# ELoad_Control_Assembly_Gen_2_-_Rev_2.net
KiCad netlist of a schematic drawn in Altium Designer
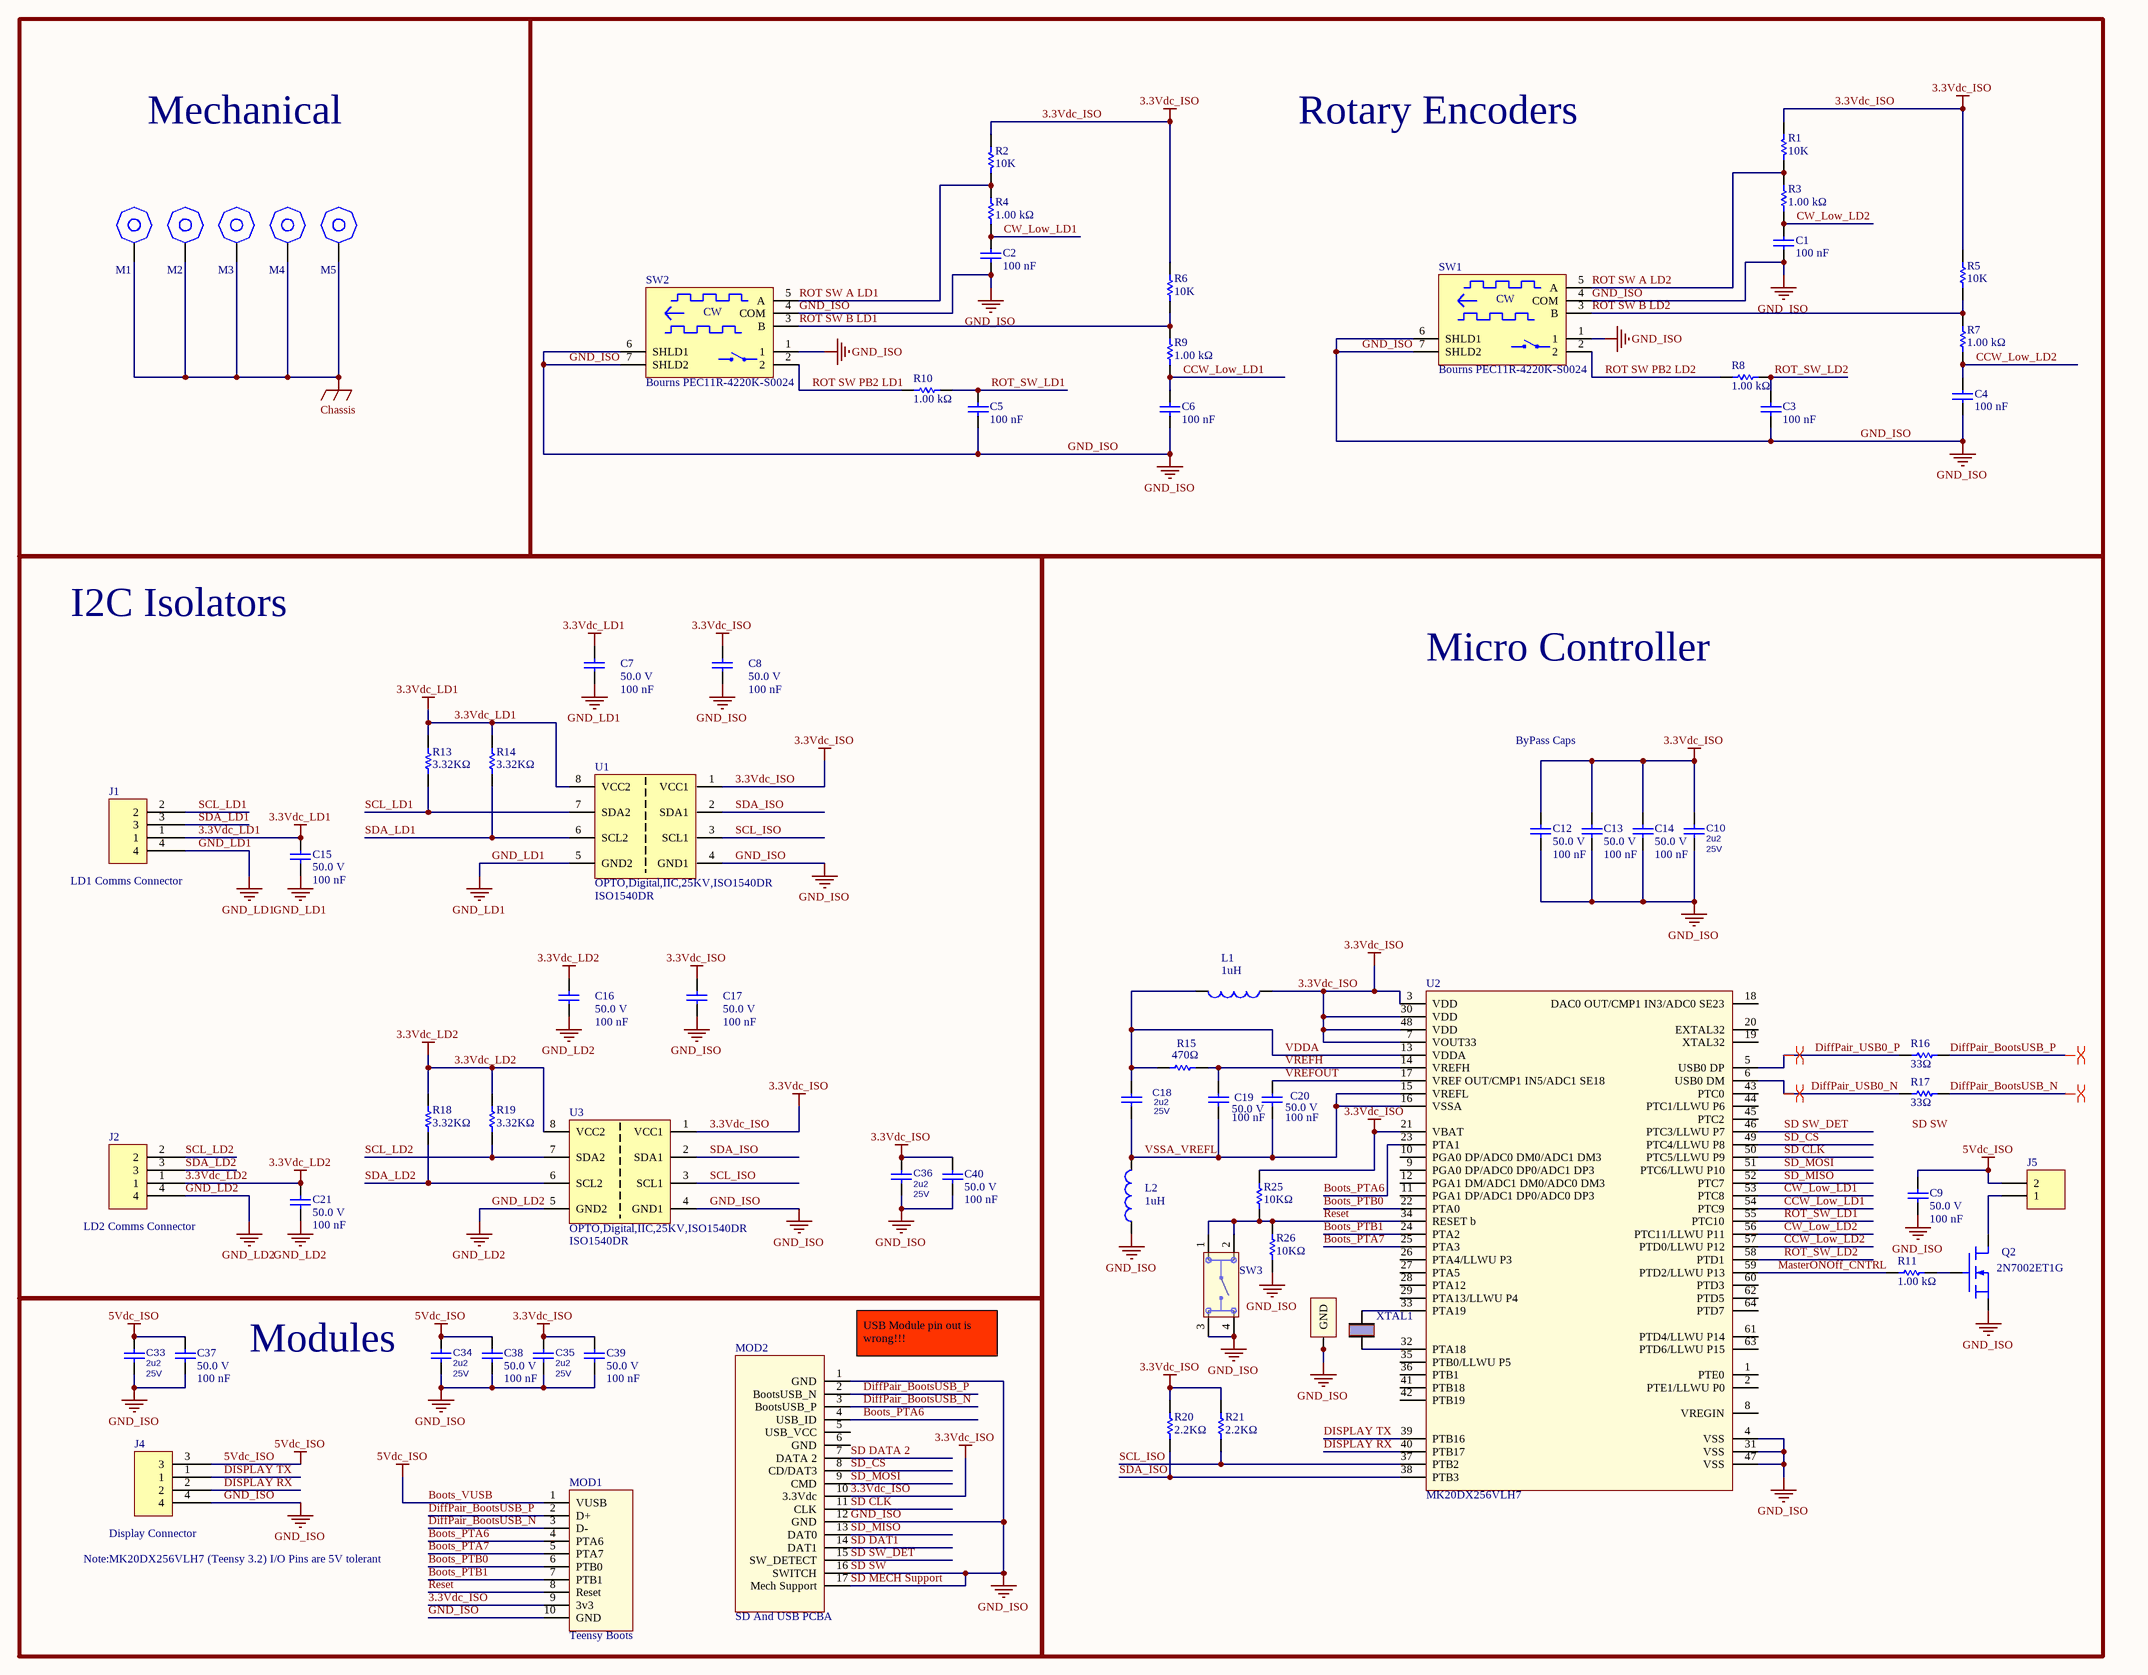
[diagram p0: ELoad Control Assembly Gen 2 - Rev 2.SchDoc]

(export (version "E")
  (design (tool "Eeschema 10.0.6"))
  (components
    (comp (ref "C1")
      (value "08055C104JAT2A")
      (footprint "CAP, 0805, HD")
      (description "Capacitor; Ceramic; Cap 0.1 uF; Tol 5%; Vol-Rtg 50 VDC; SMT; 0805; X7R; Tape & Reel")
      (fields (field (name "CAPACITANCE") "100 nF"))
      (libsource (lib "Master Oct28_2018") (part "Cap,0805,100nf,50V,5%,08055C104JAT2A"))
    )
    (comp (ref "C2")
      (value "08055C104JAT2A")
      (footprint "CAP, 0805, HD")
      (description "Capacitor; Ceramic; Cap 0.1 uF; Tol 5%; Vol-Rtg 50 VDC; SMT; 0805; X7R; Tape & Reel")
      (fields (field (name "CAPACITANCE") "100 nF"))
      (libsource (lib "Master Oct28_2018") (part "Cap,0805,100nf,50V,5%,08055C104JAT2A"))
    )
    (comp (ref "C3")
      (value "08055C104JAT2A")
      (footprint "CAP, 0805, HD")
      (description "Capacitor; Ceramic; Cap 0.1 uF; Tol 5%; Vol-Rtg 50 VDC; SMT; 0805; X7R; Tape & Reel")
      (fields (field (name "CAPACITANCE") "100 nF"))
      (libsource (lib "Master Oct28_2018") (part "Cap,0805,100nf,50V,5%,08055C104JAT2A"))
    )
    (comp (ref "C4")
      (value "08055C104JAT2A")
      (footprint "CAP, 0805, HD")
      (description "Capacitor; Ceramic; Cap 0.1 uF; Tol 5%; Vol-Rtg 50 VDC; SMT; 0805; X7R; Tape & Reel")
      (fields (field (name "CAPACITANCE") "100 nF"))
      (libsource (lib "Master Oct28_2018") (part "Cap,0805,100nf,50V,5%,08055C104JAT2A"))
    )
    (comp (ref "C5")
      (value "08055C104JAT2A")
      (footprint "CAP, 0805, HD")
      (description "Capacitor; Ceramic; Cap 0.1 uF; Tol 5%; Vol-Rtg 50 VDC; SMT; 0805; X7R; Tape & Reel")
      (fields (field (name "CAPACITANCE") "100 nF"))
      (libsource (lib "Master Oct28_2018") (part "Cap,0805,100nf,50V,5%,08055C104JAT2A"))
    )
    (comp (ref "C6")
      (value "08055C104JAT2A")
      (footprint "CAP, 0805, HD")
      (description "Capacitor; Ceramic; Cap 0.1 uF; Tol 5%; Vol-Rtg 50 VDC; SMT; 0805; X7R; Tape & Reel")
      (fields (field (name "CAPACITANCE") "100 nF"))
      (libsource (lib "Master Oct28_2018") (part "Cap,0805,100nf,50V,5%,08055C104JAT2A"))
    )
    (comp (ref "C7")
      (value "Cap")
      (footprint "Cap,0805")
      (description "Capacitor; Ceramic; Cap 0.1 uF; Tol 5%; Vol-Rtg 50 VDC; SMT; 0805; X7R; Tape & Reel")
      (fields
        (field (name "MANUFACTURER PART NUMBER") "08055C104JAT2A")
        (field (name "VOLTAGE RATING (DC)") "50.0 V")
        (field (name "CAPACITANCE") "100 nF")
      )
      (libsource (lib "Master SEPT_2019") (part "Cap,0805,100nf,50V,5%,08055C104JAT2A"))
    )
    (comp (ref "C8")
      (value "Cap")
      (footprint "Cap,0805")
      (description "Capacitor; Ceramic; Cap 0.1 uF; Tol 5%; Vol-Rtg 50 VDC; SMT; 0805; X7R; Tape & Reel")
      (fields
        (field (name "MANUFACTURER PART NUMBER") "08055C104JAT2A")
        (field (name "VOLTAGE RATING (DC)") "50.0 V")
        (field (name "CAPACITANCE") "100 nF")
      )
      (libsource (lib "Master SEPT_2019") (part "Cap,0805,100nf,50V,5%,08055C104JAT2A"))
    )
    (comp (ref "C9")
      (value "Cap")
      (footprint "Cap,0805")
      (description "Capacitor; Ceramic; Cap 0.1 uF; Tol 5%; Vol-Rtg 50 VDC; SMT; 0805; X7R; Tape & Reel")
      (fields
        (field (name "MANUFACTURER PART NUMBER") "08055C104JAT2A")
        (field (name "VOLTAGE RATING (DC)") "50.0 V")
        (field (name "CAPACITANCE") "100 nF")
      )
      (libsource (lib "Master SEPT2019") (part "Cap,0805,100nf,50V,5%,08055C104JAT2A"))
    )
    (comp (ref "C10")
      (value "2u2")
      (footprint "CAP, 0805, HD")
      (description "Cap,SMD,MLCC,2.2uF 25V X7R 10%,0805")
      (fields (field (name "MANUFACTURER") "Murata") (field (name "VOLTAGE") "25V"))
      (libsource (lib "Master SEPT2019") (part "Cap,0805,2.2uF,10%,25V"))
    )
    (comp (ref "C12")
      (value "Cap")
      (footprint "Cap,0805")
      (description "Capacitor; Ceramic; Cap 0.1 uF; Tol 5%; Vol-Rtg 50 VDC; SMT; 0805; X7R; Tape & Reel")
      (fields
        (field (name "MANUFACTURER PART NUMBER") "08055C104JAT2A")
        (field (name "VOLTAGE RATING (DC)") "50.0 V")
        (field (name "CAPACITANCE") "100 nF")
      )
      (libsource (lib "Master SEPT2019") (part "Cap,0805,100nf,50V,5%,08055C104JAT2A"))
    )
    (comp (ref "C13")
      (value "Cap")
      (footprint "Cap,0805")
      (description "Capacitor; Ceramic; Cap 0.1 uF; Tol 5%; Vol-Rtg 50 VDC; SMT; 0805; X7R; Tape & Reel")
      (fields
        (field (name "MANUFACTURER PART NUMBER") "08055C104JAT2A")
        (field (name "VOLTAGE RATING (DC)") "50.0 V")
        (field (name "CAPACITANCE") "100 nF")
      )
      (libsource (lib "Master SEPT2019") (part "Cap,0805,100nf,50V,5%,08055C104JAT2A"))
    )
    (comp (ref "C14")
      (value "Cap")
      (footprint "Cap,0805")
      (description "Capacitor; Ceramic; Cap 0.1 uF; Tol 5%; Vol-Rtg 50 VDC; SMT; 0805; X7R; Tape & Reel")
      (fields
        (field (name "MANUFACTURER PART NUMBER") "08055C104JAT2A")
        (field (name "VOLTAGE RATING (DC)") "50.0 V")
        (field (name "CAPACITANCE") "100 nF")
      )
      (libsource (lib "Master SEPT2019") (part "Cap,0805,100nf,50V,5%,08055C104JAT2A"))
    )
    (comp (ref "C15")
      (value "Cap")
      (footprint "Cap,0805")
      (description "Capacitor; Ceramic; Cap 0.1 uF; Tol 5%; Vol-Rtg 50 VDC; SMT; 0805; X7R; Tape & Reel")
      (fields
        (field (name "MANUFACTURER PART NUMBER") "08055C104JAT2A")
        (field (name "VOLTAGE RATING (DC)") "50.0 V")
        (field (name "CAPACITANCE") "100 nF")
      )
      (libsource (lib "Master SEPT_2019") (part "Cap,0805,100nf,50V,5%,08055C104JAT2A"))
    )
    (comp (ref "C16")
      (value "Cap")
      (footprint "Cap,0805")
      (description "Capacitor; Ceramic; Cap 0.1 uF; Tol 5%; Vol-Rtg 50 VDC; SMT; 0805; X7R; Tape & Reel")
      (fields
        (field (name "MANUFACTURER PART NUMBER") "08055C104JAT2A")
        (field (name "VOLTAGE RATING (DC)") "50.0 V")
        (field (name "CAPACITANCE") "100 nF")
      )
      (libsource (lib "Master SEPT_2019") (part "Cap,0805,100nf,50V,5%,08055C104JAT2A"))
    )
    (comp (ref "C17")
      (value "Cap")
      (footprint "Cap,0805")
      (description "Capacitor; Ceramic; Cap 0.1 uF; Tol 5%; Vol-Rtg 50 VDC; SMT; 0805; X7R; Tape & Reel")
      (fields
        (field (name "MANUFACTURER PART NUMBER") "08055C104JAT2A")
        (field (name "VOLTAGE RATING (DC)") "50.0 V")
        (field (name "CAPACITANCE") "100 nF")
      )
      (libsource (lib "Master SEPT_2019") (part "Cap,0805,100nf,50V,5%,08055C104JAT2A"))
    )
    (comp (ref "C18")
      (value "2u2")
      (footprint "res, 0805, HD")
      (description "Cap,SMD,MLCC,2.2uF 25V X7R 10%,0805")
      (fields (field (name "MANUFACTURER") "Murata") (field (name "VOLTAGE") "25V"))
      (libsource (lib "Master SEPT2019") (part "Cap,0805,2.2uF,10%,25V"))
    )
    (comp (ref "C19")
      (value "Cap")
      (footprint "Cap,0805")
      (description "Capacitor; Ceramic; Cap 0.1 uF; Tol 5%; Vol-Rtg 50 VDC; SMT; 0805; X7R; Tape & Reel")
      (fields
        (field (name "MANUFACTURER PART NUMBER") "08055C104JAT2A")
        (field (name "VOLTAGE RATING (DC)") "50.0 V")
        (field (name "CAPACITANCE") "100 nF")
      )
      (libsource (lib "Master SEPT2019") (part "Cap,0805,100nf,50V,5%,08055C104JAT2A"))
    )
    (comp (ref "C20")
      (value "Cap")
      (footprint "Cap,0805")
      (description "Capacitor; Ceramic; Cap 0.1 uF; Tol 5%; Vol-Rtg 50 VDC; SMT; 0805; X7R; Tape & Reel")
      (fields
        (field (name "MANUFACTURER PART NUMBER") "08055C104JAT2A")
        (field (name "VOLTAGE RATING (DC)") "50.0 V")
        (field (name "CAPACITANCE") "100 nF")
      )
      (libsource (lib "Master SEPT2019") (part "Cap,0805,100nf,50V,5%,08055C104JAT2A"))
    )
    (comp (ref "C21")
      (value "Cap")
      (footprint "Cap,0805")
      (description "Capacitor; Ceramic; Cap 0.1 uF; Tol 5%; Vol-Rtg 50 VDC; SMT; 0805; X7R; Tape & Reel")
      (fields
        (field (name "MANUFACTURER PART NUMBER") "08055C104JAT2A")
        (field (name "VOLTAGE RATING (DC)") "50.0 V")
        (field (name "CAPACITANCE") "100 nF")
      )
      (libsource (lib "Master SEPT_2019") (part "Cap,0805,100nf,50V,5%,08055C104JAT2A"))
    )
    (comp (ref "C33")
      (value "2u2")
      (footprint "CAP, 0805, HD")
      (description "Cap,SMD,MLCC,2.2uF 25V X7R 10%,0805")
      (fields (field (name "MANUFACTURER") "Murata") (field (name "VOLTAGE") "25V"))
      (libsource (lib "Master SEPT2019") (part "Cap,0805,2.2uF,10%,25V"))
    )
    (comp (ref "C34")
      (value "2u2")
      (footprint "CAP, 0805, HD")
      (description "Cap,SMD,MLCC,2.2uF 25V X7R 10%,0805")
      (fields (field (name "MANUFACTURER") "Murata") (field (name "VOLTAGE") "25V"))
      (libsource (lib "Master SEPT2019") (part "Cap,0805,2.2uF,10%,25V"))
    )
    (comp (ref "C35")
      (value "2u2")
      (footprint "CAP, 0805, HD")
      (description "Cap,SMD,MLCC,2.2uF 25V X7R 10%,0805")
      (fields (field (name "MANUFACTURER") "Murata") (field (name "VOLTAGE") "25V"))
      (libsource (lib "Master SEPT2019") (part "Cap,0805,2.2uF,10%,25V"))
    )
    (comp (ref "C36")
      (value "2u2")
      (footprint "CAP, 0805, HD")
      (description "Cap,SMD,MLCC,2.2uF 25V X7R 10%,0805")
      (fields (field (name "MANUFACTURER") "Murata") (field (name "VOLTAGE") "25V"))
      (libsource (lib "Master SEPT2019") (part "Cap,0805,2.2uF,10%,25V"))
    )
    (comp (ref "C37")
      (value "Cap")
      (footprint "Cap,0805")
      (description "Capacitor; Ceramic; Cap 0.1 uF; Tol 5%; Vol-Rtg 50 VDC; SMT; 0805; X7R; Tape & Reel")
      (fields
        (field (name "MANUFACTURER PART NUMBER") "08055C104JAT2A")
        (field (name "VOLTAGE RATING (DC)") "50.0 V")
        (field (name "CAPACITANCE") "100 nF")
      )
      (libsource (lib "Master SEPT2019") (part "Cap,0805,100nf,50V,5%,08055C104JAT2A"))
    )
    (comp (ref "C38")
      (value "Cap")
      (footprint "Cap,0805")
      (description "Capacitor; Ceramic; Cap 0.1 uF; Tol 5%; Vol-Rtg 50 VDC; SMT; 0805; X7R; Tape & Reel")
      (fields
        (field (name "MANUFACTURER PART NUMBER") "08055C104JAT2A")
        (field (name "VOLTAGE RATING (DC)") "50.0 V")
        (field (name "CAPACITANCE") "100 nF")
      )
      (libsource (lib "Master SEPT2019") (part "Cap,0805,100nf,50V,5%,08055C104JAT2A"))
    )
    (comp (ref "C39")
      (value "Cap")
      (footprint "Cap,0805")
      (description "Capacitor; Ceramic; Cap 0.1 uF; Tol 5%; Vol-Rtg 50 VDC; SMT; 0805; X7R; Tape & Reel")
      (fields
        (field (name "MANUFACTURER PART NUMBER") "08055C104JAT2A")
        (field (name "VOLTAGE RATING (DC)") "50.0 V")
        (field (name "CAPACITANCE") "100 nF")
      )
      (libsource (lib "Master SEPT2019") (part "Cap,0805,100nf,50V,5%,08055C104JAT2A"))
    )
    (comp (ref "C40")
      (value "Cap")
      (footprint "Cap,0805")
      (description "Capacitor; Ceramic; Cap 0.1 uF; Tol 5%; Vol-Rtg 50 VDC; SMT; 0805; X7R; Tape & Reel")
      (fields
        (field (name "MANUFACTURER PART NUMBER") "08055C104JAT2A")
        (field (name "VOLTAGE RATING (DC)") "50.0 V")
        (field (name "CAPACITANCE") "100 nF")
      )
      (libsource (lib "Master SEPT2019") (part "Cap,0805,100nf,50V,5%,08055C104JAT2A"))
    )
    (comp (ref "J1")
      (value "JST B4B-PH-K-S(LF)(SN)")
      (footprint "Conn, JST, 4 pin, 2mm spacing Right Angle")
      (description "PH Series 4 Position 2 mm Pitch Through Hole Crimp Top Entry Shrouded Header")
      (fields (field (name "MANUFACTURER PART NUMBER") "B4B-PH-K-S(LF)(SN)"))
      (libsource (lib "Master JULY2019") (part "Conntector, though hole, JST, 4pin, 2mm,B4B-PH-K-S(LF)(SN)"))
    )
    (comp (ref "J2")
      (value "JST B4B-PH-K-S(LF)(SN)")
      (footprint "Conn, JST, 4 pin, 2mm spacing Right Angle")
      (description "PH Series 4 Position 2 mm Pitch Through Hole Crimp Top Entry Shrouded Header")
      (fields (field (name "MANUFACTURER PART NUMBER") "B4B-PH-K-S(LF)(SN)"))
      (libsource (lib "Master JULY2019") (part "Conntector, though hole, JST, 4pin, 2mm,B4B-PH-K-S(LF)(SN)"))
    )
    (comp (ref "J4")
      (value "JST B4B-PH-K-S(LF)(SN)")
      (footprint "Conn, JST, 4 pin, 2mm spacing Right Angle")
      (description "PH Series 4 Position 2 mm Pitch Through Hole Crimp Top Entry Shrouded Header")
      (fields (field (name "MANUFACTURER PART NUMBER") "B4B-PH-K-S(LF)(SN)"))
      (libsource (lib "") (part "Conntector, though hole, JST, 4pin, 2mm,B4B-PH-K-S(LF)(SN)_1"))
    )
    (comp (ref "J5")
      (value "conn, through hole, molex, 2 pin, 0.1\",640456-2")
      (footprint "Conn, Molex, 2pin,0.1\" spacing")
      (description "Header, Friction Lock; MTA-100; 2; 250 VAC; Polyester; Tin; Copper Alloy; Tin")
      (libsource (lib "Master JULY2019") (part "conn, through hole, molex, 2 pin, 0.1{dblquote},640456-2"))
    )
    (comp (ref "L1")
      (value "BK2125HM601-T")
      (footprint "Ind, 0805")
      (description "FERRITE BEAD 600 OHM 0805 1LN")
      (fields (field (name "MANUFACTURER") "Taiyo Yuden") (field (name "INDUCTANCE") "1uH"))
      (libsource (lib "Master SEPT_2019") (part "Ind,0805,Ferrite Bead,600 Ohms @ 100MHz,BK2125HM601-T"))
    )
    (comp (ref "L2")
      (value "BK2125HM601-T")
      (footprint "Ind, 0805")
      (description "FERRITE BEAD 600 OHM 0805 1LN")
      (fields (field (name "MANUFACTURER") "Taiyo Yuden") (field (name "INDUCTANCE") "1uH"))
      (libsource (lib "Master SEPT_2019") (part "Ind,0805,Ferrite Bead,600 Ohms @ 100MHz,BK2125HM601-T"))
    )
    (comp (ref "M1")
      (value "M3 hex Standoff")
      (footprint "Standoff,Hex,M3,8mm")
      (description "HEX STANDOFF M3,generic")
      (libsource (lib "Master SEPT2019") (part "Mech,Standoff, M3, Hex"))
    )
    (comp (ref "M2")
      (value "M3 hex Standoff")
      (footprint "Standoff,Hex,M3,8mm")
      (description "HEX STANDOFF M3,generic")
      (libsource (lib "Master SEPT2019") (part "Mech,Standoff, M3, Hex"))
    )
    (comp (ref "M3")
      (value "M3 hex Standoff")
      (footprint "Standoff,Hex,M3,8mm")
      (description "HEX STANDOFF M3,generic")
      (libsource (lib "Master SEPT2019") (part "Mech,Standoff, M3, Hex"))
    )
    (comp (ref "M4")
      (value "M3 hex Standoff")
      (footprint "Standoff,Hex,M3,8mm")
      (description "HEX STANDOFF M3,generic")
      (libsource (lib "Master SEPT2019") (part "Mech,Standoff, M3, Hex"))
    )
    (comp (ref "M5")
      (value "M3 hex Standoff")
      (footprint "Standoff,Hex,M3,8mm")
      (description "HEX STANDOFF M3,generic")
      (libsource (lib "Master SEPT2019") (part "Mech,Standoff, M3, Hex"))
    )
    (comp (ref "MOD1")
      (value "Teensy Boots")
      (footprint "Mod,Teensy Boots")
      (libsource (lib "Master SEPT2019") (part "Module,Teensy Boots,Programming"))
    )
    (comp (ref "MOD2")
      (value "SD Card Connector Breakout")
      (footprint "Mod, SD and USB Connector Breakout - duplicate")
      (fields (field (name "DISCRIPTION") "SD And USB PCBA"))
      (libsource (lib "Master JULY2019") (part "Mod,SD and USB breakout, Vertical"))
    )
    (comp (ref "Q2")
      (value "2N7002ET1G")
      (footprint "SOT23-3")
      (description "Small Signal MOSFET, 60 V, 310 mA, Single, N-Channel, 3-Pin SOT-23, Pb-Free, Tape and Reel")
      (fields
        (field (name "MANUFACTURER") "ON Semiconductor")
        (field (name "MANUFACTURER PART NUMBER") "2N7002ET1G")
      )
      (libsource (lib "Master JULY2019") (part "MOSFET,N-Channel,SOT23,0.25A,60V,2N7002ET1G"))
    )
    (comp (ref "R1")
      (value "Vishay / Dale CRCW080510K0FKTA")
      (footprint "res, 0805, HD")
      (description "RES SMD 10K OHM 1% 1/8W 0805")
      (fields (field (name "RESISTANCE") "10K"))
      (libsource (lib "MasterRev3") (part "Res,0805,10.0kΩ,1%,100 ppm,CRCW080510K0FKTA"))
    )
    (comp (ref "R2")
      (value "Vishay / Dale CRCW080510K0FKTA")
      (footprint "res, 0805, HD")
      (description "RES SMD 10K OHM 1% 1/8W 0805")
      (fields (field (name "RESISTANCE") "10K"))
      (libsource (lib "MasterRev3") (part "Res,0805,10.0kΩ,1%,100 ppm,CRCW080510K0FKTA"))
    )
    (comp (ref "R3")
      (value "Vishay CRCW08051K00JNEA")
      (footprint "res, 0805, HD")
      (description "Res Thick Film 0805 1K Ohm 5% 0.125W(1/8W) ±200ppm/C Molded SMD Automotive Paper T/R")
      (fields
        (field (name "MANUFACTURER PART NUMBER") "CRCW08051K00JNEA")
        (field (name "RESISTANCE") "1.00 kΩ")
      )
      (libsource (lib "Master SEPT2019") (part "Res,0805,1.00 kΩ,5%,200ppm,CRCW08051K00JNEA"))
    )
    (comp (ref "R4")
      (value "Vishay CRCW08051K00JNEA")
      (footprint "res, 0805, HD")
      (description "Res Thick Film 0805 1K Ohm 5% 0.125W(1/8W) ±200ppm/C Molded SMD Automotive Paper T/R")
      (fields
        (field (name "MANUFACTURER PART NUMBER") "CRCW08051K00JNEA")
        (field (name "RESISTANCE") "1.00 kΩ")
      )
      (libsource (lib "Master SEPT2019") (part "Res,0805,1.00 kΩ,5%,200ppm,CRCW08051K00JNEA"))
    )
    (comp (ref "R5")
      (value "Vishay / Dale CRCW080510K0FKTA")
      (footprint "res, 0805, HD")
      (description "RES SMD 10K OHM 1% 1/8W 0805")
      (fields (field (name "RESISTANCE") "10K"))
      (libsource (lib "MasterRev3") (part "Res,0805,10.0kΩ,1%,100 ppm,CRCW080510K0FKTA"))
    )
    (comp (ref "R6")
      (value "Vishay / Dale CRCW080510K0FKTA")
      (footprint "res, 0805, HD")
      (description "RES SMD 10K OHM 1% 1/8W 0805")
      (fields (field (name "RESISTANCE") "10K"))
      (libsource (lib "MasterRev3") (part "Res,0805,10.0kΩ,1%,100 ppm,CRCW080510K0FKTA"))
    )
    (comp (ref "R7")
      (value "Vishay CRCW08051K00JNEA")
      (footprint "res, 0805, HD")
      (description "Res Thick Film 0805 1K Ohm 5% 0.125W(1/8W) ±200ppm/C Molded SMD Automotive Paper T/R")
      (fields
        (field (name "MANUFACTURER PART NUMBER") "CRCW08051K00JNEA")
        (field (name "RESISTANCE") "1.00 kΩ")
      )
      (libsource (lib "Master SEPT2019") (part "Res,0805,1.00 kΩ,5%,200ppm,CRCW08051K00JNEA"))
    )
    (comp (ref "R8")
      (value "Vishay CRCW08051K00JNEA")
      (footprint "res, 0805, HD")
      (description "Res Thick Film 0805 1K Ohm 5% 0.125W(1/8W) ±200ppm/C Molded SMD Automotive Paper T/R")
      (fields
        (field (name "MANUFACTURER PART NUMBER") "CRCW08051K00JNEA")
        (field (name "RESISTANCE") "1.00 kΩ")
      )
      (libsource (lib "Master SEPT2019") (part "Res,0805,1.00 kΩ,5%,200ppm,CRCW08051K00JNEA"))
    )
    (comp (ref "R9")
      (value "Vishay CRCW08051K00JNEA")
      (footprint "res, 0805, HD")
      (description "Res Thick Film 0805 1K Ohm 5% 0.125W(1/8W) ±200ppm/C Molded SMD Automotive Paper T/R")
      (fields
        (field (name "MANUFACTURER PART NUMBER") "CRCW08051K00JNEA")
        (field (name "RESISTANCE") "1.00 kΩ")
      )
      (libsource (lib "Master SEPT2019") (part "Res,0805,1.00 kΩ,5%,200ppm,CRCW08051K00JNEA"))
    )
    (comp (ref "R10")
      (value "Vishay CRCW08051K00JNEA")
      (footprint "res, 0805, HD")
      (description "Res Thick Film 0805 1K Ohm 5% 0.125W(1/8W) ±200ppm/C Molded SMD Automotive Paper T/R")
      (fields
        (field (name "MANUFACTURER PART NUMBER") "CRCW08051K00JNEA")
        (field (name "RESISTANCE") "1.00 kΩ")
      )
      (libsource (lib "Master SEPT2019") (part "Res,0805,1.00 kΩ,5%,200ppm,CRCW08051K00JNEA"))
    )
    (comp (ref "R11")
      (value "Vishay CRCW08051K00JNEA")
      (footprint "res, 0805, HD")
      (description "Res Thick Film 0805 1K Ohm 5% 0.125W(1/8W) ±200ppm/C Molded SMD Automotive Paper T/R")
      (fields
        (field (name "MANUFACTURER PART NUMBER") "CRCW08051K00JNEA")
        (field (name "RESISTANCE") "1.00 kΩ")
      )
      (libsource (lib "Master SEPT2019") (part "Res,0805,1.00 kΩ,5%,200ppm,CRCW08051K00JNEA"))
    )
    (comp (ref "R13")
      (value "Res1")
      (footprint "res, 0805, HD")
      (description "RES SMD 3.32K OHM 1% 1/8W 0805")
      (fields (field (name "RESISTANCE") "3.32KΩ"))
      (libsource (lib "Master JULY2019") (part "Res,0805,3.32K,±1%,100.0 ppm/°C,150.0 V,CRCW08053K32FKEA"))
    )
    (comp (ref "R14")
      (value "Res1")
      (footprint "res, 0805, HD")
      (description "RES SMD 3.32K OHM 1% 1/8W 0805")
      (fields (field (name "RESISTANCE") "3.32KΩ"))
      (libsource (lib "Master JULY2019") (part "Res,0805,3.32K,±1%,100.0 ppm/°C,150.0 V,CRCW08053K32FKEA"))
    )
    (comp (ref "R15")
      (value "Res1")
      (footprint "res, 0805, HD")
      (description "RES SMD 470 OHM 5% 1/8W 0805")
      (fields
        (field (name "MANUFACTURER") "Bourns Inc.")
        (field (name "TOLERANCE") "±5%")
        (field (name "RESISTANCE") "470Ω")
      )
      (libsource (lib "Master SEPT2019") (part "res,0805,470Ω,5%,200ppm,CR0805-JW-471ELF"))
    )
    (comp (ref "R16")
      (value "CR0805-JW-330ELF")
      (footprint "res, 0805, HD")
      (description "RES SMD 33 OHM 5% 1/8W 0805")
      (fields
        (field (name "MANUFACTURER") "Bourns Inc.")
        (field (name "TOLERANCE") "±5%")
        (field (name "RESISTANCE") "33Ω")
      )
      (libsource (lib "Master SEPT2019") (part "Res,0805,33Ω,±5%,200ppm,CR0805-JW-330ELF"))
    )
    (comp (ref "R17")
      (value "CR0805-JW-330ELF")
      (footprint "res, 0805, HD")
      (description "RES SMD 33 OHM 5% 1/8W 0805")
      (fields
        (field (name "MANUFACTURER") "Bourns Inc.")
        (field (name "TOLERANCE") "±5%")
        (field (name "RESISTANCE") "33Ω")
      )
      (libsource (lib "Master SEPT2019") (part "Res,0805,33Ω,±5%,200ppm,CR0805-JW-330ELF"))
    )
    (comp (ref "R18")
      (value "Res1")
      (footprint "res, 0805, HD")
      (description "RES SMD 3.32K OHM 1% 1/8W 0805")
      (fields (field (name "RESISTANCE") "3.32KΩ"))
      (libsource (lib "Master JULY2019") (part "Res,0805,3.32K,±1%,100.0 ppm/°C,150.0 V,CRCW08053K32FKEA"))
    )
    (comp (ref "R19")
      (value "Res1")
      (footprint "res, 0805, HD")
      (description "RES SMD 3.32K OHM 1% 1/8W 0805")
      (fields (field (name "RESISTANCE") "3.32KΩ"))
      (libsource (lib "Master JULY2019") (part "Res,0805,3.32K,±1%,100.0 ppm/°C,150.0 V,CRCW08053K32FKEA"))
    )
    (comp (ref "R20")
      (value "Res1")
      (footprint "res, 0805, HD")
      (description "RES SMD 2.2K OHM 1% 1/8W 0805")
      (fields (field (name "RESISTANCE") "2.2KΩ"))
      (libsource (lib "Master JULY2019") (part "Res,0805,2.2KΩ,±1%,100.0 ppm/°C,150.0 V,CRCW08052K20FKEA"))
    )
    (comp (ref "R21")
      (value "Res1")
      (footprint "res, 0805, HD")
      (description "RES SMD 2.2K OHM 1% 1/8W 0805")
      (fields (field (name "RESISTANCE") "2.2KΩ"))
      (libsource (lib "Master JULY2019") (part "Res,0805,2.2KΩ,±1%,100.0 ppm/°C,150.0 V,CRCW08052K20FKEA"))
    )
    (comp (ref "R25")
      (value "Vishay / Dale CRCW080510K0FKTA")
      (footprint "res, 0805, HD")
      (description "RES SMD 10K OHM 1% 1/8W 0805")
      (fields (field (name "RESISTANCE") "10KΩ"))
      (libsource (lib "Master JULY2019") (part "Res,0805,10.0kΩ,1%,100 ppm,CRCW080510K0FKTA"))
    )
    (comp (ref "R26")
      (value "Vishay / Dale CRCW080510K0FKTA")
      (footprint "res, 0805, HD")
      (description "RES SMD 10K OHM 1% 1/8W 0805")
      (fields (field (name "RESISTANCE") "10KΩ"))
      (libsource (lib "Master JULY2019") (part "Res,0805,10.0kΩ,1%,100 ppm,CRCW080510K0FKTA"))
    )
    (comp (ref "SW1")
      (value "Bourns PEC11R-4220K-S0024")
      (footprint "Rotary encoder")
      (description "24 Pulse Incremental Mechanical Rotary Encoder w/ 6 mm Knurl Shaft, Through Hole")
      (libsource (lib "Master JULY2019") (part "Rotary encoder, PEC11R-4220K-S0024"))
    )
    (comp (ref "SW2")
      (value "Bourns PEC11R-4220K-S0024")
      (footprint "Rotary encoder")
      (description "24 Pulse Incremental Mechanical Rotary Encoder w/ 6 mm Knurl Shaft, Through Hole")
      (libsource (lib "Master JULY2019") (part "Rotary encoder, PEC11R-4220K-S0024"))
    )
    (comp (ref "SW3")
      (value "Switch, push button,N.O. DPST,SKRPACE010")
      (footprint "Switch Tactile N.O. SPST Button")
      (description "Switch Tactile N.O. SPST Button J-Bend 0.05A 16VDC 2.55N SMD Automotive T/R")
      (libsource (lib "Master JULY2019") (part "Switch, push button,N.O. DPST,SKRPACE010"))
    )
    (comp (ref "U1")
      (value "OPTO,Digital,IIC,25KV,ISO1540DR")
      (footprint "SOIC-8")
      (description "DGTL ISO 2.5KV 2CH I2C 8SOIC")
      (fields (field (name "MANUFACTURER PART NUMBER 1") "ISO1540DR"))
      (libsource (lib "Master JUL_2019-Shawn") (part "OPTO,Digital,IIC,25KV,ISO1540DR"))
    )
    (comp (ref "U2")
      (value "MK20DX256VLH7")
      (footprint "LQFP-64")
      (description "ARM Cortex-M4 Kinetis K20 Microcontroller IC 32-Bit 72MHz 256KB (256K x 8) FLASH 64-LQFP (10x10)")
      (fields (field (name "MANUFACTURER") "NXP") (field (name "MFG P/N") "MK20DX256VLH7"))
      (libsource (lib "Master SEPT2019") (part "Micro,72Mhz,32-Bit,256Kmem,Teensy3.2,MK20DX256VLH7"))
    )
    (comp (ref "U3")
      (value "OPTO,Digital,IIC,25KV,ISO1540DR")
      (footprint "SOIC-8")
      (description "DGTL ISO 2.5KV 2CH I2C 8SOIC")
      (fields (field (name "MANUFACTURER PART NUMBER 1") "ISO1540DR"))
      (libsource (lib "Master JUL_2019-Shawn") (part "OPTO,Digital,IIC,25KV,ISO1540DR"))
    )
    (comp (ref "XTAL1")
      (value "NX3225SA-16.000000MHZ-B3")
      (footprint "CRYSTAL,4-SMD, No Lead")
      (description "CRYSTAL 16.0000MHZ 7.2PF SMD")
      (fields (field (name "MANUFACTURER") "NDK America, Inc."))
      (libsource (lib "Master JULY2019") (part "resonator,crystal,SMD,stab15ppm,Tol,10ppm,7.2pf,80ohms,NX3225SA-16.000000MHZ-B3"))
    )
  )
  (nets
    (net (code "1") (name "/Boots_PTA6") (class "Default")
      (node (ref "MOD1") (pin "4") (pinfunction "PTA6_4") (pintype "passive"))
      (node (ref "MOD2") (pin "4") (pinfunction "USB_ID_4") (pintype "passive"))
      (node (ref "U2") (pin "23") (pinfunction "PTA1_23") (pintype "passive"))
    )
    (net (code "2") (name "/Boots_PTA7") (class "Default")
      (node (ref "MOD1") (pin "5") (pinfunction "PTA7_5") (pintype "passive"))
      (node (ref "U2") (pin "25") (pinfunction "PTA3_25") (pintype "passive"))
    )
    (net (code "3") (name "/Boots_PTB0") (class "Default")
      (node (ref "MOD1") (pin "6") (pinfunction "PTB0_6") (pintype "passive"))
      (node (ref "U2") (pin "22") (pinfunction "PTA0_22") (pintype "passive"))
    )
    (net (code "4") (name "/Boots_PTB1") (class "Default")
      (node (ref "MOD1") (pin "7") (pinfunction "PTB1_7") (pintype "passive"))
      (node (ref "U2") (pin "24") (pinfunction "PTA2_24") (pintype "passive"))
    )
    (net (code "5") (name "/CCW_Low_LD1") (class "Default")
      (node (ref "C6") (pin "2") (pinfunction "2_2") (pintype "passive"))
      (node (ref "R9") (pin "2") (pinfunction "2_2") (pintype "passive"))
      (node (ref "U2") (pin "54") (pinfunction "PTC9_54") (pintype "passive"))
    )
    (net (code "6") (name "/CCW_Low_LD2") (class "Default")
      (node (ref "C4") (pin "2") (pinfunction "2_2") (pintype "passive"))
      (node (ref "R7") (pin "2") (pinfunction "2_2") (pintype "passive"))
      (node (ref "U2") (pin "57") (pinfunction "PTD0/LLWU_P12_57") (pintype "passive"))
    )
    (net (code "7") (name "/CW_Low_LD1") (class "Default")
      (node (ref "C2") (pin "2") (pinfunction "2_2") (pintype "passive"))
      (node (ref "R4") (pin "2") (pinfunction "2_2") (pintype "passive"))
      (node (ref "U2") (pin "53") (pinfunction "PTC8_53") (pintype "passive"))
    )
    (net (code "8") (name "/CW_Low_LD2") (class "Default")
      (node (ref "C1") (pin "2") (pinfunction "2_2") (pintype "passive"))
      (node (ref "R3") (pin "2") (pinfunction "2_2") (pintype "passive"))
      (node (ref "U2") (pin "56") (pinfunction "PTC11/LLWU_P11_56") (pintype "passive"))
    )
    (net (code "9") (name "/DISPLAY RX") (class "Default")
      (node (ref "J4") (pin "2") (pinfunction "2_2") (pintype "passive"))
      (node (ref "U2") (pin "40") (pinfunction "PTB17_40") (pintype "passive"))
    )
    (net (code "10") (name "/DISPLAY TX") (class "Default")
      (node (ref "J4") (pin "1") (pinfunction "1_1") (pintype "passive"))
      (node (ref "U2") (pin "39") (pinfunction "PTB16_39") (pintype "passive"))
    )
    (net (code "11") (name "/DiffPair_BootsUSB_N") (class "Default")
      (node (ref "MOD1") (pin "3") (pinfunction "D-_3") (pintype "passive"))
      (node (ref "MOD2") (pin "3") (pinfunction "BootsUSB_P_3") (pintype "passive"))
      (node (ref "R17") (pin "1") (pinfunction "1_1") (pintype "passive"))
    )
    (net (code "12") (name "/DiffPair_BootsUSB_P") (class "Default")
      (node (ref "MOD1") (pin "2") (pinfunction "D+_2") (pintype "passive"))
      (node (ref "MOD2") (pin "2") (pinfunction "BootsUSB_N_2") (pintype "passive"))
      (node (ref "R16") (pin "1") (pinfunction "1_1") (pintype "passive"))
    )
    (net (code "13") (name "/DiffPair_USB0_N") (class "Default")
      (node (ref "R17") (pin "2") (pinfunction "2_2") (pintype "passive"))
      (node (ref "U2") (pin "6") (pinfunction "USB0_DM_6") (pintype "passive"))
    )
    (net (code "14") (name "/DiffPair_USB0_P") (class "Default")
      (node (ref "R16") (pin "2") (pinfunction "2_2") (pintype "passive"))
      (node (ref "U2") (pin "5") (pinfunction "USB0_DP_5") (pintype "passive"))
    )
    (net (code "15") (name "/MasterO~{N}Off_CNTRL") (class "Default")
      (node (ref "R11") (pin "1") (pinfunction "1_1") (pintype "passive"))
      (node (ref "U2") (pin "59") (pinfunction "PTD2/LLWU_P13_59") (pintype "passive"))
    )
    (net (code "16") (name "/ROT SW A LD1") (class "Default")
      (node (ref "R2") (pin "1") (pinfunction "1_1") (pintype "passive"))
      (node (ref "R4") (pin "1") (pinfunction "1_1") (pintype "passive"))
      (node (ref "SW2") (pin "5") (pinfunction "A_5") (pintype "passive"))
    )
    (net (code "17") (name "/ROT SW A LD2") (class "Default")
      (node (ref "R1") (pin "1") (pinfunction "1_1") (pintype "passive"))
      (node (ref "R3") (pin "1") (pinfunction "1_1") (pintype "passive"))
      (node (ref "SW1") (pin "5") (pinfunction "A_5") (pintype "passive"))
    )
    (net (code "18") (name "/ROT SW B LD1") (class "Default")
      (node (ref "R6") (pin "2") (pinfunction "2_2") (pintype "passive"))
      (node (ref "R9") (pin "1") (pinfunction "1_1") (pintype "passive"))
      (node (ref "SW2") (pin "3") (pinfunction "B_3") (pintype "passive"))
    )
    (net (code "19") (name "/ROT SW B LD2") (class "Default")
      (node (ref "R5") (pin "2") (pinfunction "2_2") (pintype "passive"))
      (node (ref "R7") (pin "1") (pinfunction "1_1") (pintype "passive"))
      (node (ref "SW1") (pin "3") (pinfunction "B_3") (pintype "passive"))
    )
    (net (code "20") (name "/ROT SW PB2 LD1") (class "Default")
      (node (ref "R10") (pin "1") (pinfunction "1_1") (pintype "passive"))
      (node (ref "SW2") (pin "2") (pinfunction "2_2") (pintype "passive"))
    )
    (net (code "21") (name "/ROT SW PB2 LD2") (class "Default")
      (node (ref "R8") (pin "1") (pinfunction "1_1") (pintype "passive"))
      (node (ref "SW1") (pin "2") (pinfunction "2_2") (pintype "passive"))
    )
    (net (code "22") (name "/ROT_SW_LD1") (class "Default")
      (node (ref "C5") (pin "2") (pinfunction "2_2") (pintype "passive"))
      (node (ref "R10") (pin "2") (pinfunction "2_2") (pintype "passive"))
      (node (ref "U2") (pin "55") (pinfunction "PTC10_55") (pintype "passive"))
    )
    (net (code "23") (name "/ROT_SW_LD2") (class "Default")
      (node (ref "C3") (pin "2") (pinfunction "2_2") (pintype "passive"))
      (node (ref "R8") (pin "2") (pinfunction "2_2") (pintype "passive"))
      (node (ref "U2") (pin "58") (pinfunction "PTD1_58") (pintype "passive"))
    )
    (net (code "24") (name "/Reset") (class "Default")
      (node (ref "MOD1") (pin "8") (pinfunction "Reset_8") (pintype "passive"))
      (node (ref "R25") (pin "1") (pinfunction "1_1") (pintype "passive"))
      (node (ref "R26") (pin "2") (pinfunction "2_2") (pintype "passive"))
      (node (ref "SW3") (pin "1") (pinfunction "1_1") (pintype "passive"))
      (node (ref "SW3") (pin "2") (pinfunction "2_2") (pintype "passive"))
      (node (ref "U2") (pin "34") (pinfunction "RESET_b_34") (pintype "passive"))
    )
    (net (code "25") (name "/SCL_ISO") (class "Default")
      (node (ref "R21") (pin "1") (pinfunction "1_1") (pintype "passive"))
      (node (ref "U1") (pin "3") (pinfunction "SCL1_3") (pintype "passive"))
      (node (ref "U2") (pin "37") (pinfunction "PTB2_37") (pintype "passive"))
      (node (ref "U3") (pin "3") (pinfunction "SCL1_3") (pintype "passive"))
    )
    (net (code "26") (name "/SCL_LD1") (class "Default")
      (node (ref "J1") (pin "2") (pinfunction "2_2") (pintype "passive"))
      (node (ref "R13") (pin "1") (pinfunction "1_1") (pintype "passive"))
      (node (ref "U1") (pin "7") (pinfunction "SDA2_7") (pintype "passive"))
    )
    (net (code "27") (name "/SCL_LD2") (class "Default")
      (node (ref "J2") (pin "2") (pinfunction "2_2") (pintype "passive"))
      (node (ref "R19") (pin "1") (pinfunction "1_1") (pintype "passive"))
      (node (ref "U3") (pin "7") (pinfunction "SDA2_7") (pintype "passive"))
    )
    (net (code "28") (name "/SD CLK") (class "Default")
      (node (ref "MOD2") (pin "11") (pinfunction "CLK_11") (pintype "passive"))
      (node (ref "U2") (pin "50") (pinfunction "PTC5/LLWU_P9_50") (pintype "passive"))
    )
    (net (code "29") (name "/SD DAT1") (class "Default")
      (node (ref "MOD2") (pin "14") (pinfunction "DAT1_14") (pintype "passive"))
    )
    (net (code "30") (name "/SD DATA 2") (class "Default")
      (node (ref "MOD2") (pin "7") (pinfunction "DATA_2_7") (pintype "passive"))
    )
    (net (code "31") (name "/SD SW_DET") (class "Default")
      (node (ref "MOD2") (pin "15") (pinfunction "SW_DETECT_15") (pintype "passive"))
      (node (ref "U2") (pin "46") (pinfunction "PTC3/LLWU_P7_46") (pintype "passive"))
    )
    (net (code "32") (name "/SDA_ISO") (class "Default")
      (node (ref "R20") (pin "1") (pinfunction "1_1") (pintype "passive"))
      (node (ref "U1") (pin "2") (pinfunction "SDA1_2") (pintype "passive"))
      (node (ref "U2") (pin "38") (pinfunction "PTB3_38") (pintype "passive"))
      (node (ref "U3") (pin "2") (pinfunction "SDA1_2") (pintype "passive"))
    )
    (net (code "33") (name "/SDA_LD1") (class "Default")
      (node (ref "J1") (pin "3") (pinfunction "3_3") (pintype "passive"))
      (node (ref "R14") (pin "1") (pinfunction "1_1") (pintype "passive"))
      (node (ref "U1") (pin "6") (pinfunction "SCL2_6") (pintype "passive"))
    )
    (net (code "34") (name "/SDA_LD2") (class "Default")
      (node (ref "J2") (pin "3") (pinfunction "3_3") (pintype "passive"))
      (node (ref "R18") (pin "1") (pinfunction "1_1") (pintype "passive"))
      (node (ref "U3") (pin "6") (pinfunction "SCL2_6") (pintype "passive"))
    )
    (net (code "35") (name "/SD_CS") (class "Default")
      (node (ref "MOD2") (pin "8") (pinfunction "CD/DAT3_8") (pintype "passive"))
      (node (ref "U2") (pin "49") (pinfunction "PTC4/LLWU_P8_49") (pintype "passive"))
    )
    (net (code "36") (name "/SD_MISO") (class "Default")
      (node (ref "MOD2") (pin "13") (pinfunction "DAT0_13") (pintype "passive"))
      (node (ref "U2") (pin "52") (pinfunction "PTC7_52") (pintype "passive"))
    )
    (net (code "37") (name "/SD_MOSI") (class "Default")
      (node (ref "MOD2") (pin "9") (pinfunction "CMD_9") (pintype "passive"))
      (node (ref "U2") (pin "51") (pinfunction "PTC6/LLWU_P10_51") (pintype "passive"))
    )
    (net (code "38") (name "/VDDA") (class "Default")
      (node (ref "C18") (pin "2") (pintype "passive"))
      (node (ref "L1") (pin "2") (pinfunction "2_2") (pintype "passive"))
      (node (ref "R15") (pin "2") (pinfunction "2_2") (pintype "passive"))
      (node (ref "U2") (pin "13") (pinfunction "VDDA_13") (pintype "passive"))
    )
    (net (code "39") (name "/VREFH") (class "Default")
      (node (ref "C19") (pin "2") (pinfunction "2_2") (pintype "passive"))
      (node (ref "R15") (pin "1") (pinfunction "1_1") (pintype "passive"))
      (node (ref "U2") (pin "14") (pinfunction "VREFH_14") (pintype "passive"))
    )
    (net (code "40") (name "/VREFOUT") (class "Default")
      (node (ref "C20") (pin "2") (pinfunction "2_2") (pintype "passive"))
      (node (ref "U2") (pin "17") (pinfunction "VREF_OUT/CMP1_IN5/ADC1_SE18_17") (pintype "passive"))
    )
    (net (code "41") (name "/VSSA_VREFL") (class "Default")
      (node (ref "C18") (pin "1") (pintype "passive"))
      (node (ref "C19") (pin "1") (pinfunction "1_1") (pintype "passive"))
      (node (ref "C20") (pin "1") (pinfunction "1_1") (pintype "passive"))
      (node (ref "L2") (pin "2") (pinfunction "2_2") (pintype "passive"))
      (node (ref "U2") (pin "15") (pinfunction "VREFL_15") (pintype "passive"))
      (node (ref "U2") (pin "16") (pinfunction "VSSA_16") (pintype "passive"))
    )
    (net (code "42") (name "3.3Vdc_ISO") (class "Default")
      (node (ref "C10") (pin "2") (pintype "passive"))
      (node (ref "C12") (pin "2") (pinfunction "2_2") (pintype "passive"))
      (node (ref "C13") (pin "2") (pinfunction "2_2") (pintype "passive"))
      (node (ref "C14") (pin "2") (pinfunction "2_2") (pintype "passive"))
      (node (ref "C17") (pin "2") (pinfunction "2_2") (pintype "passive"))
      (node (ref "C35") (pin "2") (pintype "passive"))
      (node (ref "C36") (pin "2") (pintype "passive"))
      (node (ref "C39") (pin "2") (pinfunction "2_2") (pintype "passive"))
      (node (ref "C40") (pin "2") (pinfunction "2_2") (pintype "passive"))
      (node (ref "C8") (pin "2") (pinfunction "2_2") (pintype "passive"))
      (node (ref "L1") (pin "1") (pinfunction "1_1") (pintype "passive"))
      (node (ref "MOD1") (pin "9") (pinfunction "3v3_9") (pintype "passive"))
      (node (ref "MOD2") (pin "10") (pinfunction "3.3Vdc_10") (pintype "passive"))
      (node (ref "R1") (pin "2") (pinfunction "2_2") (pintype "passive"))
      (node (ref "R2") (pin "2") (pinfunction "2_2") (pintype "passive"))
      (node (ref "R20") (pin "2") (pinfunction "2_2") (pintype "passive"))
      (node (ref "R21") (pin "2") (pinfunction "2_2") (pintype "passive"))
      (node (ref "R25") (pin "2") (pinfunction "2_2") (pintype "passive"))
      (node (ref "R5") (pin "1") (pinfunction "1_1") (pintype "passive"))
      (node (ref "R6") (pin "1") (pinfunction "1_1") (pintype "passive"))
      (node (ref "U1") (pin "1") (pinfunction "VCC1_1") (pintype "passive"))
      (node (ref "U2") (pin "21") (pinfunction "VBAT_21") (pintype "passive"))
      (node (ref "U2") (pin "3") (pinfunction "VDD_3") (pintype "passive"))
      (node (ref "U2") (pin "30") (pinfunction "VDD_30") (pintype "passive"))
      (node (ref "U2") (pin "48") (pinfunction "VDD_48") (pintype "passive"))
      (node (ref "U2") (pin "7") (pinfunction "VOUT33_7") (pintype "passive"))
      (node (ref "U3") (pin "1") (pinfunction "VCC1_1") (pintype "passive"))
    )
    (net (code "43") (name "3.3Vdc_LD1") (class "Default")
      (node (ref "C15") (pin "2") (pinfunction "2_2") (pintype "passive"))
      (node (ref "C7") (pin "2") (pinfunction "2_2") (pintype "passive"))
      (node (ref "J1") (pin "1") (pinfunction "1_1") (pintype "passive"))
      (node (ref "R13") (pin "2") (pinfunction "2_2") (pintype "passive"))
      (node (ref "R14") (pin "2") (pinfunction "2_2") (pintype "passive"))
      (node (ref "U1") (pin "8") (pinfunction "VCC2_8") (pintype "passive"))
    )
    (net (code "44") (name "3.3Vdc_LD2") (class "Default")
      (node (ref "C16") (pin "2") (pinfunction "2_2") (pintype "passive"))
      (node (ref "C21") (pin "2") (pinfunction "2_2") (pintype "passive"))
      (node (ref "J2") (pin "1") (pinfunction "1_1") (pintype "passive"))
      (node (ref "R18") (pin "2") (pinfunction "2_2") (pintype "passive"))
      (node (ref "R19") (pin "2") (pinfunction "2_2") (pintype "passive"))
      (node (ref "U3") (pin "8") (pinfunction "VCC2_8") (pintype "passive"))
    )
    (net (code "45") (name "5Vdc_ISO") (class "Default")
      (node (ref "C33") (pin "2") (pintype "passive"))
      (node (ref "C34") (pin "2") (pintype "passive"))
      (node (ref "C37") (pin "2") (pinfunction "2_2") (pintype "passive"))
      (node (ref "C38") (pin "2") (pinfunction "2_2") (pintype "passive"))
      (node (ref "C9") (pin "2") (pinfunction "2_2") (pintype "passive"))
      (node (ref "J4") (pin "3") (pinfunction "3_3") (pintype "passive"))
      (node (ref "J5") (pin "2") (pinfunction "2_2") (pintype "passive"))
      (node (ref "MOD1") (pin "1") (pinfunction "VUSB_1") (pintype "passive"))
    )
    (net (code "46") (name "Chassis") (class "Default")
      (node (ref "M1") (pin "0") (pinfunction "0_0") (pintype "passive"))
      (node (ref "M2") (pin "0") (pinfunction "0_0") (pintype "passive"))
      (node (ref "M3") (pin "0") (pinfunction "0_0") (pintype "passive"))
      (node (ref "M4") (pin "0") (pinfunction "0_0") (pintype "passive"))
      (node (ref "M5") (pin "0") (pinfunction "0_0") (pintype "passive"))
    )
    (net (code "47") (name "GND_ISO") (class "Default")
      (node (ref "C1") (pin "1") (pinfunction "1_1") (pintype "passive"))
      (node (ref "C10") (pin "1") (pintype "passive"))
      (node (ref "C12") (pin "1") (pinfunction "1_1") (pintype "passive"))
      (node (ref "C13") (pin "1") (pinfunction "1_1") (pintype "passive"))
      (node (ref "C14") (pin "1") (pinfunction "1_1") (pintype "passive"))
      (node (ref "C17") (pin "1") (pinfunction "1_1") (pintype "passive"))
      (node (ref "C2") (pin "1") (pinfunction "1_1") (pintype "passive"))
      (node (ref "C3") (pin "1") (pinfunction "1_1") (pintype "passive"))
      (node (ref "C33") (pin "1") (pintype "passive"))
      (node (ref "C34") (pin "1") (pintype "passive"))
      (node (ref "C35") (pin "1") (pintype "passive"))
      (node (ref "C36") (pin "1") (pintype "passive"))
      (node (ref "C37") (pin "1") (pinfunction "1_1") (pintype "passive"))
      (node (ref "C38") (pin "1") (pinfunction "1_1") (pintype "passive"))
      (node (ref "C39") (pin "1") (pinfunction "1_1") (pintype "passive"))
      (node (ref "C4") (pin "1") (pinfunction "1_1") (pintype "passive"))
      (node (ref "C40") (pin "1") (pinfunction "1_1") (pintype "passive"))
      (node (ref "C5") (pin "1") (pinfunction "1_1") (pintype "passive"))
      (node (ref "C6") (pin "1") (pinfunction "1_1") (pintype "passive"))
      (node (ref "C8") (pin "1") (pinfunction "1_1") (pintype "passive"))
      (node (ref "C9") (pin "1") (pinfunction "1_1") (pintype "passive"))
      (node (ref "J4") (pin "4") (pinfunction "4_4") (pintype "passive"))
      (node (ref "L2") (pin "1") (pinfunction "1_1") (pintype "passive"))
      (node (ref "MOD1") (pin "10") (pinfunction "GND_10") (pintype "passive"))
      (node (ref "MOD2") (pin "1") (pinfunction "GND_1") (pintype "passive"))
      (node (ref "MOD2") (pin "12") (pinfunction "GND_12") (pintype "passive"))
      (node (ref "MOD2") (pin "16") (pinfunction "SWITCH_16") (pintype "passive"))
      (node (ref "MOD2") (pin "17") (pinfunction "Mech_Support_17") (pintype "passive"))
      (node (ref "Q2") (pin "2") (pinfunction "S_2") (pintype "passive"))
      (node (ref "R26") (pin "1") (pinfunction "1_1") (pintype "passive"))
      (node (ref "SW1") (pin "1") (pinfunction "1_1") (pintype "passive"))
      (node (ref "SW1") (pin "4") (pinfunction "COM_4") (pintype "passive"))
      (node (ref "SW1") (pin "6") (pinfunction "SHLD1_6") (pintype "passive"))
      (node (ref "SW1") (pin "7") (pinfunction "SHLD2_7") (pintype "passive"))
      (node (ref "SW2") (pin "1") (pinfunction "1_1") (pintype "passive"))
      (node (ref "SW2") (pin "4") (pinfunction "COM_4") (pintype "passive"))
      (node (ref "SW2") (pin "6") (pinfunction "SHLD1_6") (pintype "passive"))
      (node (ref "SW2") (pin "7") (pinfunction "SHLD2_7") (pintype "passive"))
      (node (ref "SW3") (pin "3") (pinfunction "3_3") (pintype "passive"))
      (node (ref "SW3") (pin "4") (pinfunction "4_4") (pintype "passive"))
      (node (ref "U1") (pin "4") (pinfunction "GND1_4") (pintype "passive"))
      (node (ref "U2") (pin "31") (pinfunction "VSS_31") (pintype "passive"))
      (node (ref "U2") (pin "4") (pinfunction "VSS_4") (pintype "passive"))
      (node (ref "U2") (pin "47") (pinfunction "VSS_47") (pintype "passive"))
      (node (ref "U3") (pin "4") (pinfunction "GND1_4") (pintype "passive"))
      (node (ref "XTAL1") (pin "2") (pinfunction "GND_2") (pintype "passive"))
      (node (ref "XTAL1") (pin "4") (pinfunction "4_4") (pintype "passive"))
    )
    (net (code "48") (name "GND_LD1") (class "Default")
      (node (ref "C15") (pin "1") (pinfunction "1_1") (pintype "passive"))
      (node (ref "C7") (pin "1") (pinfunction "1_1") (pintype "passive"))
      (node (ref "J1") (pin "4") (pinfunction "4_4") (pintype "passive"))
      (node (ref "U1") (pin "5") (pinfunction "GND2_5") (pintype "passive"))
    )
    (net (code "49") (name "GND_LD2") (class "Default")
      (node (ref "C16") (pin "1") (pinfunction "1_1") (pintype "passive"))
      (node (ref "C21") (pin "1") (pinfunction "1_1") (pintype "passive"))
      (node (ref "J2") (pin "4") (pinfunction "4_4") (pintype "passive"))
      (node (ref "U3") (pin "5") (pinfunction "GND2_5") (pintype "passive"))
    )
    (net (code "50") (name "Net-(Q2-D)") (class "Default")
      (node (ref "J5") (pin "1") (pinfunction "1_1") (pintype "passive"))
      (node (ref "Q2") (pin "3") (pinfunction "D_3") (pintype "passive"))
    )
    (net (code "51") (name "Net-(Q2-G)") (class "Default")
      (node (ref "Q2") (pin "1") (pinfunction "G_1") (pintype "passive"))
      (node (ref "R11") (pin "2") (pinfunction "2_2") (pintype "passive"))
    )
    (net (code "52") (name "Net-(U2-PTA18)") (class "Default")
      (node (ref "U2") (pin "32") (pinfunction "PTA18_32") (pintype "passive"))
      (node (ref "XTAL1") (pin "3") (pinfunction "3_3") (pintype "passive"))
    )
    (net (code "53") (name "Net-(U2-PTA19)") (class "Default")
      (node (ref "U2") (pin "33") (pinfunction "PTA19_33") (pintype "passive"))
      (node (ref "XTAL1") (pin "1") (pinfunction "1_1") (pintype "passive"))
    )
    (net (code "54") (name "unconnected-(MOD2-GND-Pad6)") (class "Default")
      (node (ref "MOD2") (pin "6") (pinfunction "GND_6") (pintype "passive"))
    )
    (net (code "55") (name "unconnected-(MOD2-USB_VCC-Pad5)") (class "Default")
      (node (ref "MOD2") (pin "5") (pinfunction "USB_VCC_5") (pintype "passive"))
    )
    (net (code "56") (name "unconnected-(U2-DAC0_OUT{slash}CMP1_IN3{slash}ADC0_SE23-Pad18)") (class "Default")
      (node (ref "U2") (pin "18") (pinfunction "DAC0_OUT/CMP1_IN3/ADC0_SE23_18") (pintype "passive"))
    )
    (net (code "57") (name "unconnected-(U2-EXTAL32-Pad20)") (class "Default")
      (node (ref "U2") (pin "20") (pinfunction "EXTAL32_20") (pintype "passive"))
    )
    (net (code "58") (name "unconnected-(U2-PGA0_DP{slash}ADC0_DM0{slash}ADC1_DM3-Pad10)") (class "Default")
      (node (ref "U2") (pin "10") (pinfunction "PGA0_DP/ADC0_DM0/ADC1_DM3_10") (pintype "passive"))
    )
    (net (code "59") (name "unconnected-(U2-PGA0_DP{slash}ADC0_DP0{slash}ADC1_DP3-Pad9)") (class "Default")
      (node (ref "U2") (pin "9") (pinfunction "PGA0_DP/ADC0_DP0/ADC1_DP3_9") (pintype "passive"))
    )
    (net (code "60") (name "unconnected-(U2-PGA1_DM{slash}ADC1_DM0{slash}ADC0_DM3-Pad12)") (class "Default")
      (node (ref "U2") (pin "12") (pinfunction "PGA1_DM/ADC1_DM0/ADC0_DM3_12") (pintype "passive"))
    )
    (net (code "61") (name "unconnected-(U2-PGA1_DP{slash}ADC1_DP0{slash}ADC0_DP3-Pad11)") (class "Default")
      (node (ref "U2") (pin "11") (pinfunction "PGA1_DP/ADC1_DP0/ADC0_DP3_11") (pintype "passive"))
    )
    (net (code "62") (name "unconnected-(U2-PTA4{slash}LLWU_P3-Pad26)") (class "Default")
      (node (ref "U2") (pin "26") (pinfunction "PTA4/LLWU_P3_26") (pintype "passive"))
    )
    (net (code "63") (name "unconnected-(U2-PTA5-Pad27)") (class "Default")
      (node (ref "U2") (pin "27") (pinfunction "PTA5_27") (pintype "passive"))
    )
    (net (code "64") (name "unconnected-(U2-PTA12-Pad28)") (class "Default")
      (node (ref "U2") (pin "28") (pinfunction "PTA12_28") (pintype "passive"))
    )
    (net (code "65") (name "unconnected-(U2-PTA13{slash}LLWU_P4-Pad29)") (class "Default")
      (node (ref "U2") (pin "29") (pinfunction "PTA13/LLWU_P4_29") (pintype "passive"))
    )
    (net (code "66") (name "unconnected-(U2-PTB0{slash}LLWU_P5-Pad35)") (class "Default")
      (node (ref "U2") (pin "35") (pinfunction "PTB0/LLWU_P5_35") (pintype "passive"))
    )
    (net (code "67") (name "unconnected-(U2-PTB1-Pad36)") (class "Default")
      (node (ref "U2") (pin "36") (pinfunction "PTB1_36") (pintype "passive"))
    )
    (net (code "68") (name "unconnected-(U2-PTB18-Pad41)") (class "Default")
      (node (ref "U2") (pin "41") (pinfunction "PTB18_41") (pintype "passive"))
    )
    (net (code "69") (name "unconnected-(U2-PTB19-Pad42)") (class "Default")
      (node (ref "U2") (pin "42") (pinfunction "PTB19_42") (pintype "passive"))
    )
    (net (code "70") (name "unconnected-(U2-PTC0-Pad43)") (class "Default")
      (node (ref "U2") (pin "43") (pinfunction "PTC0_43") (pintype "passive"))
    )
    (net (code "71") (name "unconnected-(U2-PTC1{slash}LLWU_P6-Pad44)") (class "Default")
      (node (ref "U2") (pin "44") (pinfunction "PTC1/LLWU_P6_44") (pintype "passive"))
    )
    (net (code "72") (name "unconnected-(U2-PTC2-Pad45)") (class "Default")
      (node (ref "U2") (pin "45") (pinfunction "PTC2_45") (pintype "passive"))
    )
    (net (code "73") (name "unconnected-(U2-PTD3-Pad60)") (class "Default")
      (node (ref "U2") (pin "60") (pinfunction "PTD3_60") (pintype "passive"))
    )
    (net (code "74") (name "unconnected-(U2-PTD4{slash}LLWU_P14-Pad61)") (class "Default")
      (node (ref "U2") (pin "61") (pinfunction "PTD4/LLWU_P14_61") (pintype "passive"))
    )
    (net (code "75") (name "unconnected-(U2-PTD5-Pad62)") (class "Default")
      (node (ref "U2") (pin "62") (pinfunction "PTD5_62") (pintype "passive"))
    )
    (net (code "76") (name "unconnected-(U2-PTD6{slash}LLWU_P15-Pad63)") (class "Default")
      (node (ref "U2") (pin "63") (pinfunction "PTD6/LLWU_P15_63") (pintype "passive"))
    )
    (net (code "77") (name "unconnected-(U2-PTD7-Pad64)") (class "Default")
      (node (ref "U2") (pin "64") (pinfunction "PTD7_64") (pintype "passive"))
    )
    (net (code "78") (name "unconnected-(U2-PTE0-Pad1)") (class "Default")
      (node (ref "U2") (pin "1") (pinfunction "PTE0_1") (pintype "passive"))
    )
    (net (code "79") (name "unconnected-(U2-PTE1{slash}LLWU_P0-Pad2)") (class "Default")
      (node (ref "U2") (pin "2") (pinfunction "PTE1/LLWU_P0_2") (pintype "passive"))
    )
    (net (code "80") (name "unconnected-(U2-VREGIN-Pad8)") (class "Default")
      (node (ref "U2") (pin "8") (pinfunction "VREGIN_8") (pintype "passive"))
    )
    (net (code "81") (name "unconnected-(U2-XTAL32-Pad19)") (class "Default")
      (node (ref "U2") (pin "19") (pinfunction "XTAL32_19") (pintype "passive"))
    )
  )
)
